# High-FrequencyOp-AmpTransimpedanceCircui.net
KiCad netlist of a schematic drawn in Altium Designer
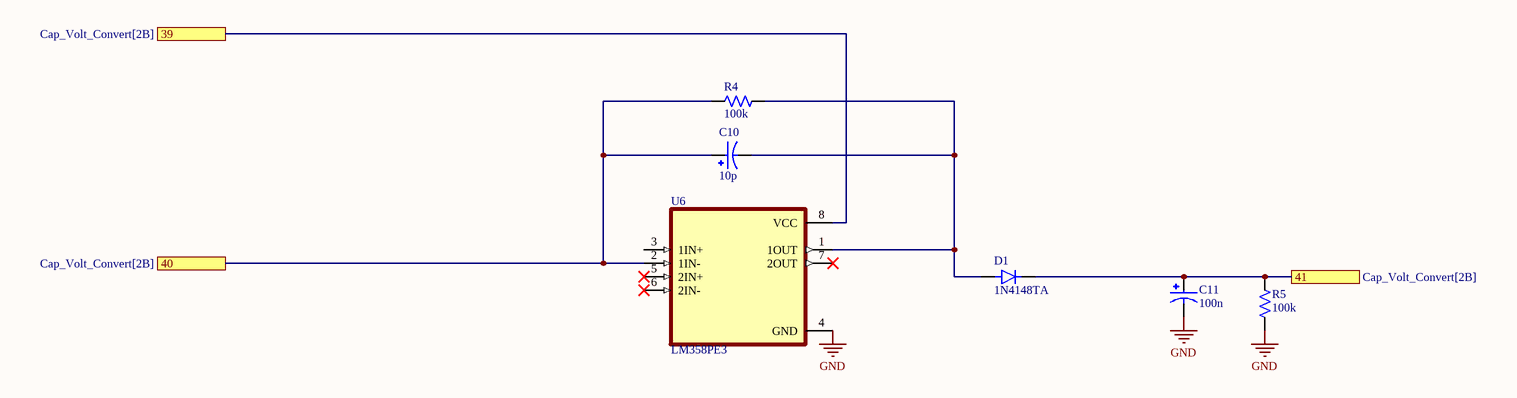
[diagram p0: High-FrequencyOp-AmpTransimpedanceCircuit.SchDoc]

(export (version "E")
  (design (tool "Eeschema 10.0.6"))
  (components
    (comp (ref "C10")
      (value "10p")
      (footprint "CAPPRD750W80D1600H2000")
      (description "CAP ALUM 680UF 20% 63V THRU HOLE")
      (fields (field (name "MP") "EEU-FS1J681S") (field (name "MF") "Panasonic Electronic Components"))
      (libsource (lib "") (part "EEUFS1J681S_1"))
    )
    (comp (ref "C11")
      (value "100n")
      (footprint "CAPPRD750W80D1600H2000")
      (description "CAP ALUM 680UF 20% 63V THRU HOLE")
      (fields (field (name "MP") "EEU-FS1J681S") (field (name "MF") "Panasonic Electronic Components"))
      (libsource (lib "Schlib1") (part "EEUFS1J681S"))
    )
    (comp (ref "D1")
      (value "1N4148TA")
      (footprint "DIOAD753W49L380D172B")
      (description "Diode Standard 100 V 200mA Through Hole DO-35")
      (fields (field (name "MF") "ON Semiconductor"))
      (libsource (lib "Schlib1") (part "1N4148TA"))
    )
    (comp (ref "R4")
      (value "100k")
      (footprint "RESAD730W45L370D210")
      (description "Metal Film Resistors - Through Hole")
      (fields (field (name "MF") "YAGEO") (field (name "MP") "MFR-12FTE52-12K5"))
      (libsource (lib "Schlib1") (part "MFR-12FTE52-12K5"))
    )
    (comp (ref "R5")
      (value "100k")
      (footprint "RESAD730W45L370D210")
      (description "Metal Film Resistors - Through Hole")
      (fields (field (name "MF") "YAGEO") (field (name "MP") "MFR-12FTE52-12K5"))
      (libsource (lib "Schlib1") (part "MFR-12FTE52-12K5"))
    )
    (comp (ref "U6")
      (value "LM358PE3")
      (footprint "DIP794W45P254L959H508Q8 - duplicate")
      (description "Dual, 30-V, 700-kHz operational amplifier")
      (fields (field (name "MF") "Texas Instruments"))
      (libsource (lib "Schlib1") (part "LM358PE3"))
    )
  )
  (nets
    (net (code "1") (name "/39") (class "Default")
      (node (ref "U6") (pin "8") (pinfunction "VCC_8") (pintype "power_in"))
    )
    (net (code "2") (name "/40") (class "Default")
      (node (ref "C10") (pin "P") (pinfunction "P_P") (pintype "passive"))
      (node (ref "R4") (pin "1") (pinfunction "1_1") (pintype "passive"))
      (node (ref "U6") (pin "2") (pinfunction "1IN-_2") (pintype "input"))
    )
    (net (code "3") (name "/41") (class "Default")
      (node (ref "C11") (pin "P") (pinfunction "P_P") (pintype "passive"))
      (node (ref "D1") (pin "K") (pinfunction "K_K") (pintype "passive"))
      (node (ref "R5") (pin "2") (pinfunction "2_2") (pintype "passive"))
    )
    (net (code "4") (name "GND") (class "Default")
      (node (ref "C11") (pin "N") (pinfunction "N_N") (pintype "passive"))
      (node (ref "R5") (pin "1") (pinfunction "1_1") (pintype "passive"))
      (node (ref "U6") (pin "4") (pinfunction "GND_4") (pintype "power_in"))
    )
    (net (code "5") (name "Net-(U6-1OUT)") (class "Default")
      (node (ref "C10") (pin "N") (pinfunction "N_N") (pintype "passive"))
      (node (ref "D1") (pin "A") (pinfunction "A_A") (pintype "passive"))
      (node (ref "R4") (pin "2") (pinfunction "2_2") (pintype "passive"))
      (node (ref "U6") (pin "1") (pinfunction "1OUT_1") (pintype "output"))
    )
    (net (code "6") (name "unconnected-(U6-1IN+-Pad3)") (class "Default")
      (node (ref "U6") (pin "3") (pinfunction "1IN+_3") (pintype "input"))
    )
    (net (code "7") (name "unconnected-(U6-2IN+-Pad5)") (class "Default")
      (node (ref "U6") (pin "5") (pinfunction "2IN+_5") (pintype "input+no_connect"))
    )
    (net (code "8") (name "unconnected-(U6-2IN--Pad6)") (class "Default")
      (node (ref "U6") (pin "6") (pinfunction "2IN-_6") (pintype "input+no_connect"))
    )
    (net (code "9") (name "unconnected-(U6-2OUT-Pad7)") (class "Default")
      (node (ref "U6") (pin "7") (pinfunction "2OUT_7") (pintype "output+no_connect"))
    )
  )
)
